# USBToTTL.net
KiCad netlist of a schematic drawn in Altium Designer
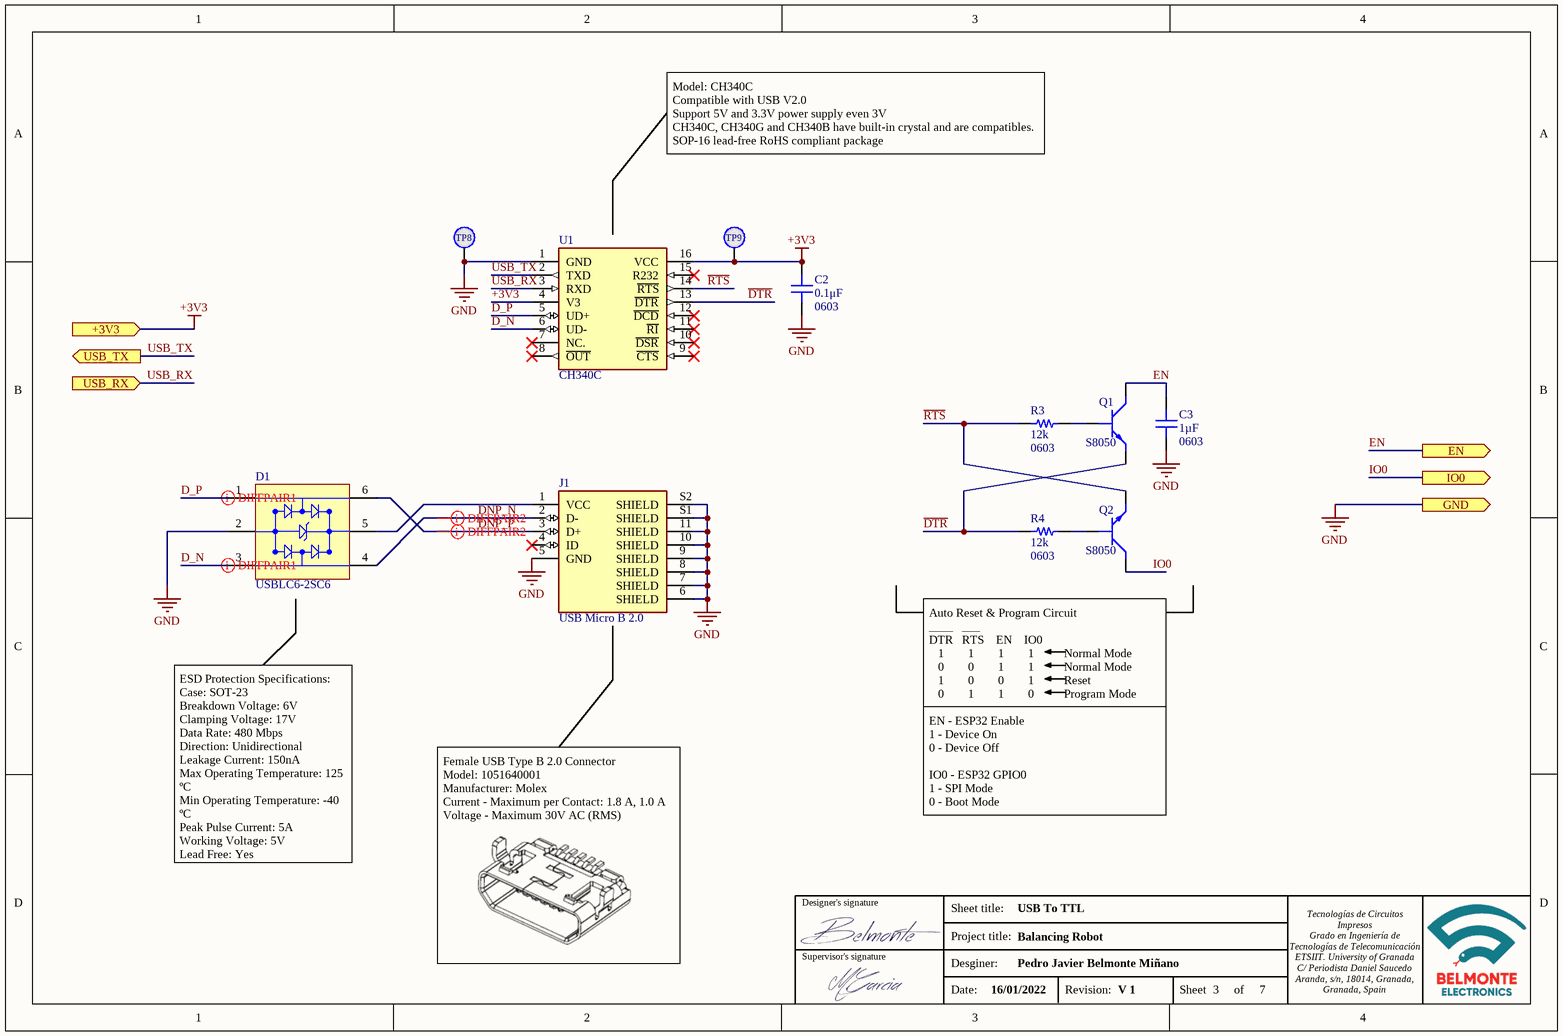
[diagram p0: USBToTTL.SchDoc]

(export (version "E")
  (design (tool "Eeschema 10.0.6"))
  (components
    (comp (ref "C2")
      (value "0.1μF")
      (footprint "FP-C0603C-CF-MFG")
      (description "CAP CER 0.1UF 50V X7R 0603")
      (fields
        (field (name "TOLERANCE") "0.1")
        (field (name "MANUFACTURER") "KEMET")
        (field (name "PACKAGE") "0603")
      )
      (libsource (lib "ControlBoard") (part "CMP-2006-03061-2"))
    )
    (comp (ref "C3")
      (value "1µF")
      (footprint "CAP 0603_1608")
      (description "CAP CER 0603 1UF 16V X7R 10%")
      (fields
        (field (name "PART NUMBER") "C0603C105K4RACAUTO")
        (field (name "MANUFACTURER") "KEMET")
        (field (name "SIZE") "0603")
      )
      (libsource (lib "ControlBoard") (part "C0603C105K4RACAUTO"))
    )
    (comp (ref "D1")
      (value "USBLC6-2SC6")
      (footprint "STM-SOT23-6L_V")
      (description "Very low capacitance ESD protection, 3.5 pF, -40 to 125 degC, 6-Pin SOT23, RoHS, Tape and Reel")
      (fields (field (name "MANUFACTURER") "STMicroelectronics"))
      (libsource (lib "ControlBoard") (part "CMP-2000-05378-1"))
    )
    (comp (ref "J1")
      (value "USB Micro B 2.0")
      (footprint "AMPHENOL_10103594-0001LF")
      (description "USB - micro B USB 2.0 Receptacle Connector 5 Position Surface Mount, Right Angle; Through Hole")
      (fields (field (name "MP") "10103594-0001LF") (field (name "MF") "Amphenol ICC (FCI)"))
      (libsource (lib "ControlBoard") (part "10103594-0001LF"))
    )
    (comp (ref "Q1")
      (value "S8050")
      (footprint "SamacSys:SOT95P240X115-3N")
      (description "Transistor")
      (libsource (lib "Robot") (part "S8050"))
    )
    (comp (ref "Q2")
      (value "S8050")
      (footprint "SamacSys:SOT95P240X115-3N")
      (description "Transistor")
      (libsource (lib "Robot") (part "S8050"))
    )
    (comp (ref "R3")
      (value "12k")
      (footprint "RES 0603_1608")
      (description "RES 12K OHM 5% 1/10W 0603")
      (fields
        (field (name "PART NUMBER") "RMCF0603JT12K0")
        (field (name "MANUFACTURER") "Stackpole Electronics Inc")
        (field (name "SIZE") "0603")
      )
      (libsource (lib "ControlBoard") (part "RMCF0603JT12K0"))
    )
    (comp (ref "R4")
      (value "12k")
      (footprint "RES 0603_1608")
      (description "RES 12K OHM 5% 1/10W 0603")
      (fields
        (field (name "PART NUMBER") "RMCF0603JT12K0")
        (field (name "MANUFACTURER") "Stackpole Electronics Inc")
        (field (name "SIZE") "0603")
      )
      (libsource (lib "ControlBoard") (part "RMCF0603JT12K0"))
    )
    (comp (ref "TP8")
      (value "Test point")
      (footprint "TestPoint")
      (libsource (lib "ControlBoard") (part "TestPoint"))
    )
    (comp (ref "TP9")
      (value "Test point")
      (footprint "TestPoint")
      (libsource (lib "ControlBoard") (part "TestPoint"))
    )
    (comp (ref "U1")
      (value "CH340C")
      (footprint "SOIC127P600X180-16N")
      (description "USB to serial chip CH340")
      (fields (field (name "MF") "WCH"))
      (libsource (lib "ControlBoard") (part "CH340C"))
    )
  )
  (nets
    (net (code "1") (name "+3V3") (class "Default")
      (node (ref "C2") (pin "2") (pinfunction "2_2") (pintype "passive"))
      (node (ref "TP9") (pin "1") (pinfunction "_1_1") (pintype "passive"))
      (node (ref "U1") (pin "16") (pinfunction "VCC_16") (pintype "power_in"))
      (node (ref "U1") (pin "4") (pinfunction "V3_4") (pintype "power_in"))
    )
    (net (code "2") (name "/DNP_N") (class "Default")
      (node (ref "D1") (pin "4") (pinfunction "I/O_3_4") (pintype "passive"))
      (node (ref "J1") (pin "2") (pinfunction "D-_2") (pintype "bidirectional"))
    )
    (net (code "3") (name "/DNP_P") (class "Default")
      (node (ref "D1") (pin "6") (pinfunction "I/O_4_6") (pintype "passive"))
      (node (ref "J1") (pin "3") (pinfunction "D+_3") (pintype "bidirectional"))
    )
    (net (code "4") (name "/D_N") (class "Default")
      (node (ref "D1") (pin "3") (pinfunction "I/O_2_3") (pintype "passive"))
      (node (ref "U1") (pin "6") (pinfunction "UD-_6") (pintype "bidirectional"))
    )
    (net (code "5") (name "/D_P") (class "Default")
      (node (ref "D1") (pin "1") (pinfunction "I/O_1_1") (pintype "passive"))
      (node (ref "U1") (pin "5") (pinfunction "UD+_5") (pintype "bidirectional"))
    )
    (net (code "6") (name "/EN") (class "Default")
      (node (ref "C3") (pin "1") (pinfunction "1_1") (pintype "passive"))
      (node (ref "Q1") (pin "2") (pinfunction "C_2") (pintype "passive"))
    )
    (net (code "7") (name "/IO0") (class "Default")
      (node (ref "Q2") (pin "2") (pinfunction "C_2") (pintype "passive"))
    )
    (net (code "8") (name "/USB_RX") (class "Default")
      (node (ref "U1") (pin "3") (pinfunction "RXD_3") (pintype "input"))
    )
    (net (code "9") (name "/USB_TX") (class "Default")
      (node (ref "U1") (pin "2") (pinfunction "TXD_2") (pintype "output"))
    )
    (net (code "10") (name "/~{DTR}") (class "Default")
      (node (ref "Q1") (pin "3") (pinfunction "E_3") (pintype "passive"))
      (node (ref "R4") (pin "1") (pinfunction "1_1") (pintype "passive"))
      (node (ref "U1") (pin "13") (pinfunction "~{DTR}_13") (pintype "output"))
    )
    (net (code "11") (name "/~{RTS}") (class "Default")
      (node (ref "Q2") (pin "3") (pinfunction "E_3") (pintype "passive"))
      (node (ref "R3") (pin "1") (pinfunction "1_1") (pintype "passive"))
      (node (ref "U1") (pin "14") (pinfunction "~{RTS}_14") (pintype "output"))
    )
    (net (code "12") (name "GND") (class "Default")
      (node (ref "C2") (pin "1") (pinfunction "1_1") (pintype "passive"))
      (node (ref "C3") (pin "2") (pinfunction "2_2") (pintype "passive"))
      (node (ref "D1") (pin "2") (pinfunction "GND_2") (pintype "passive"))
      (node (ref "J1") (pin "10") (pinfunction "SHIELD_10") (pintype "passive"))
      (node (ref "J1") (pin "11") (pinfunction "SHIELD_11") (pintype "passive"))
      (node (ref "J1") (pin "5") (pinfunction "GND_5") (pintype "power_in"))
      (node (ref "J1") (pin "6") (pinfunction "SHIELD_6") (pintype "passive"))
      (node (ref "J1") (pin "7") (pinfunction "SHIELD_7") (pintype "passive"))
      (node (ref "J1") (pin "8") (pinfunction "SHIELD_8") (pintype "passive"))
      (node (ref "J1") (pin "9") (pinfunction "SHIELD_9") (pintype "passive"))
      (node (ref "J1") (pin "S1") (pinfunction "SHIELD_S1") (pintype "passive"))
      (node (ref "J1") (pin "S2") (pinfunction "SHIELD_S2") (pintype "passive"))
      (node (ref "TP8") (pin "1") (pinfunction "_1_1") (pintype "passive"))
      (node (ref "U1") (pin "1") (pinfunction "GND_1") (pintype "power_in"))
    )
    (net (code "13") (name "Net-(D1-VBUS)") (class "Default")
      (node (ref "D1") (pin "5") (pinfunction "VBUS_5") (pintype "passive"))
      (node (ref "J1") (pin "1") (pinfunction "VCC_1") (pintype "power_in"))
    )
    (net (code "14") (name "Net-(Q1-B)") (class "Default")
      (node (ref "Q1") (pin "1") (pinfunction "B_1") (pintype "passive"))
      (node (ref "R3") (pin "2") (pinfunction "2_2") (pintype "passive"))
    )
    (net (code "15") (name "Net-(Q2-B)") (class "Default")
      (node (ref "Q2") (pin "1") (pinfunction "B_1") (pintype "passive"))
      (node (ref "R4") (pin "2") (pinfunction "2_2") (pintype "passive"))
    )
    (net (code "16") (name "unconnected-(J1-ID-Pad4)") (class "Default")
      (node (ref "J1") (pin "4") (pinfunction "ID_4") (pintype "bidirectional+no_connect"))
    )
    (net (code "17") (name "unconnected-(U1-NC.-Pad7)") (class "Default")
      (node (ref "U1") (pin "7") (pinfunction "NC._7") (pintype "passive+no_connect"))
    )
    (net (code "18") (name "unconnected-(U1-R232-Pad15)") (class "Default")
      (node (ref "U1") (pin "15") (pinfunction "R232_15") (pintype "input+no_connect"))
    )
    (net (code "19") (name "unconnected-(U1-~{CTS}-Pad9)") (class "Default")
      (node (ref "U1") (pin "9") (pinfunction "~{CTS}_9") (pintype "input+no_connect"))
    )
    (net (code "20") (name "unconnected-(U1-~{DCD}-Pad12)") (class "Default")
      (node (ref "U1") (pin "12") (pinfunction "~{DCD}_12") (pintype "input+no_connect"))
    )
    (net (code "21") (name "unconnected-(U1-~{DSR}-Pad10)") (class "Default")
      (node (ref "U1") (pin "10") (pinfunction "~{DSR}_10") (pintype "input+no_connect"))
    )
    (net (code "22") (name "unconnected-(U1-~{OUT}-Pad8)") (class "Default")
      (node (ref "U1") (pin "8") (pinfunction "~{OUT}_8") (pintype "output+no_connect"))
    )
    (net (code "23") (name "unconnected-(U1-~{RI}-Pad11)") (class "Default")
      (node (ref "U1") (pin "11") (pinfunction "~{RI}_11") (pintype "input+no_connect"))
    )
  )
)
